# Createathon_2018.net
KiCad netlist of a schematic drawn in EAGLE
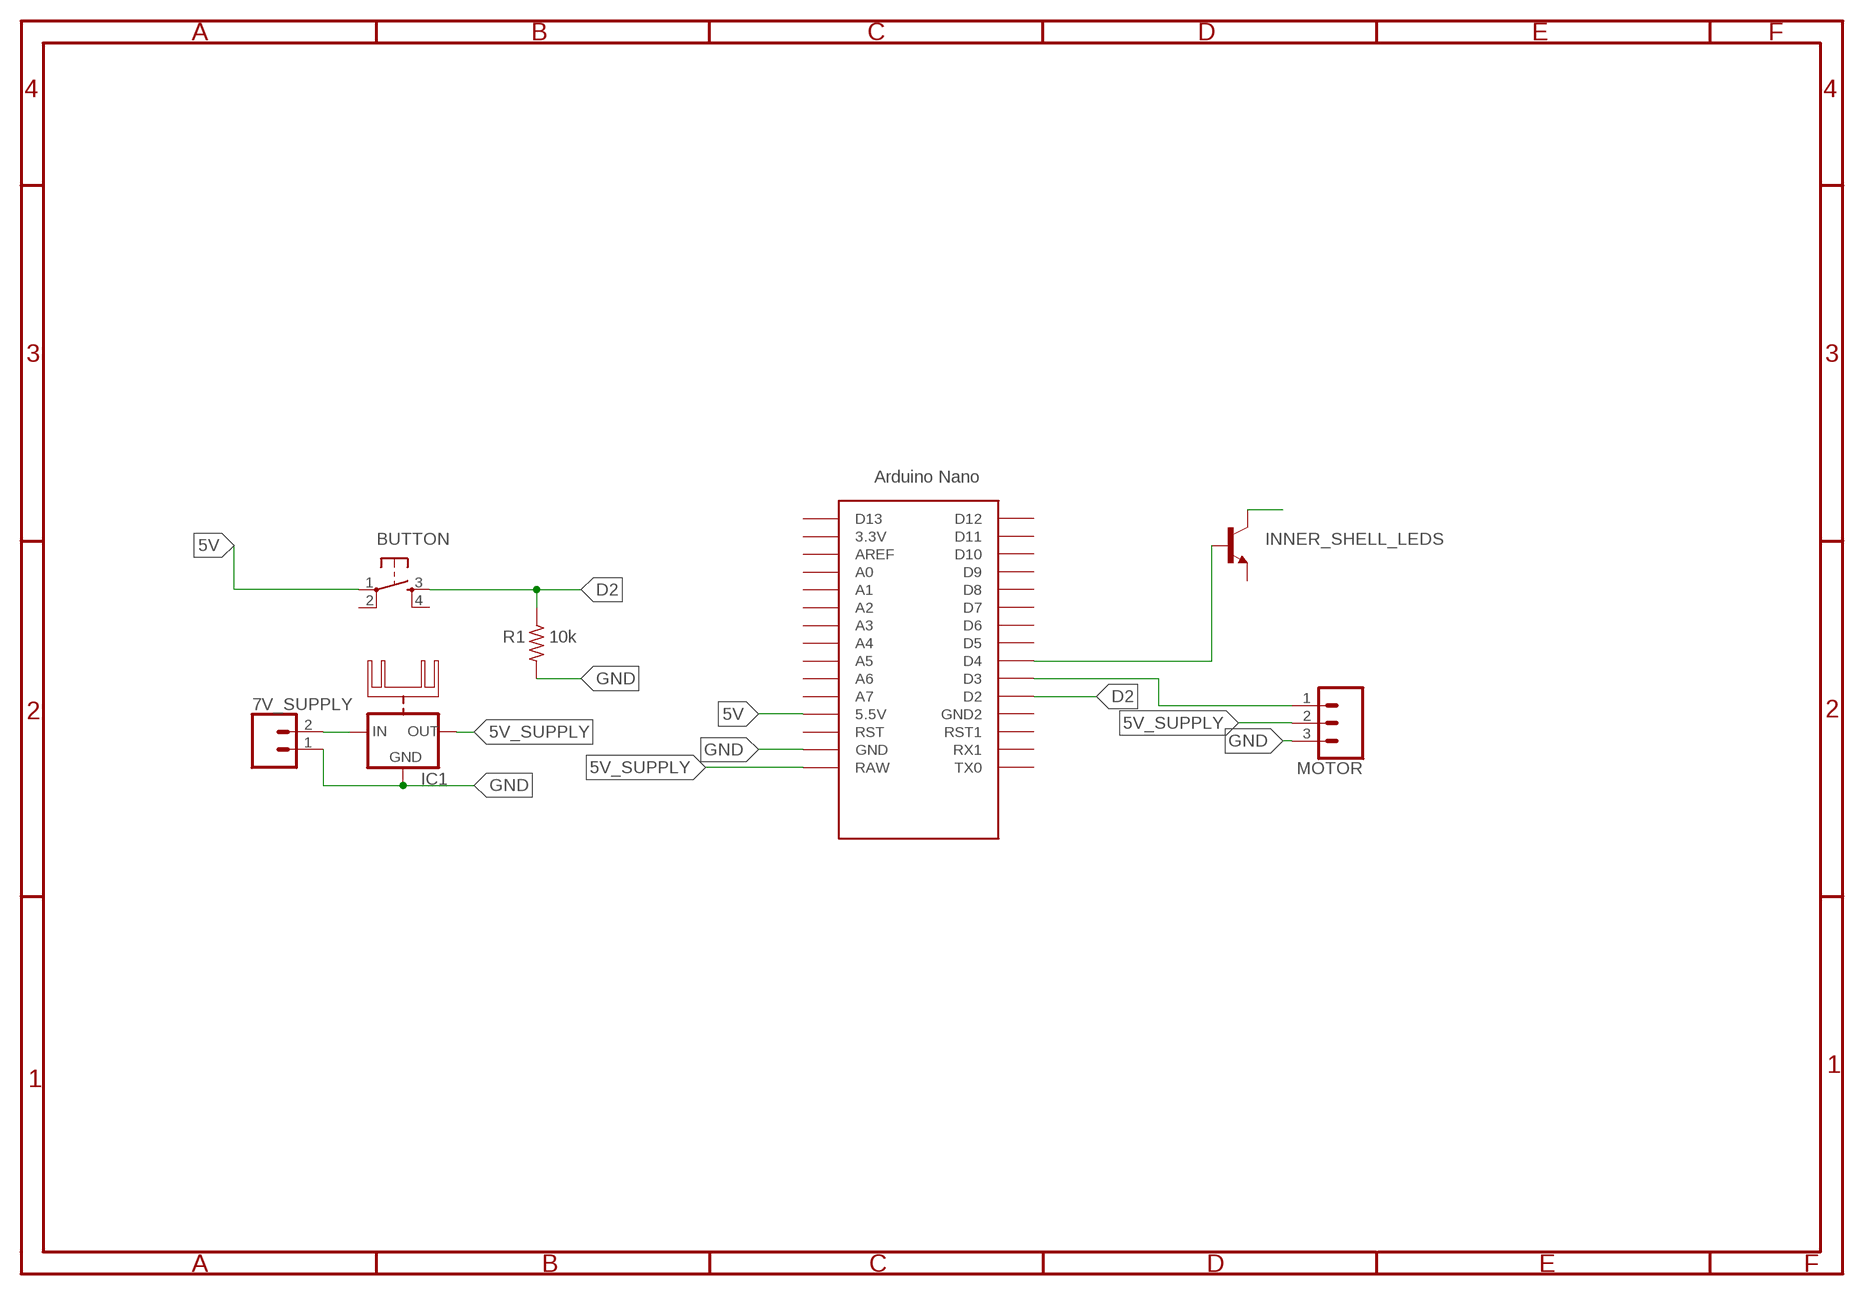
[diagram p0: schematic, sheet 1]

(export (version "E")
  (design (tool "Eeschema 10.0.6"))
  (components
    (comp (ref "7V_SUPPLY")
      (value "CONN_02")
      (footprint "eagle-import:1X02")
      (libsource (lib "eagle-import") (part "CONN_02"))
    )
    (comp (ref "BUTTON")
      (value "TAC_SWITCHPTH")
      (footprint "eagle-import:TACTILE-PTH")
      (libsource (lib "eagle-import") (part "TAC_SWITCHPTH"))
    )
    (comp (ref "IC1")
      (value "78XXH")
      (footprint "eagle-import:78XXH")
      (libsource (lib "eagle-import") (part "78XXH"))
    )
    (comp (ref "INNER_SHELL_LEDS")
      (value "TRANSISTOR_NPNTO92")
      (footprint "eagle-import:TO-92")
      (libsource (lib "eagle-import") (part "TRANSISTOR_NPNTO92"))
    )
    (comp (ref "MOTOR")
      (value "CONN_03")
      (footprint "eagle-import:1X03")
      (libsource (lib "eagle-import") (part "CONN_03"))
    )
    (comp (ref "R1")
      (value "10k")
      (footprint "eagle-import:0204_7")
      (libsource (lib "eagle-import") (part "R-US_0204/7"))
    )
    (comp (ref "U$1")
      (value "NANO")
      (footprint "eagle-import:NANO")
      (libsource (lib "eagle-import") (part "NANO"))
    )
  )
  (nets
    (net (code "1") (name "5V") (class "Default")
      (node (ref "BUTTON") (pin "1") (pinfunction "1_1") (pintype "passive"))
      (node (ref "U$1") (pin "5V") (pinfunction "5.5V_5V") (pintype "bidirectional"))
    )
    (net (code "2") (name "5V_SUPPLY") (class "Default")
      (node (ref "IC1") (pin "OUT") (pinfunction "OUT_OUT") (pintype "passive"))
      (node (ref "MOTOR") (pin "2") (pinfunction "2_2") (pintype "passive"))
      (node (ref "U$1") (pin "RAW") (pinfunction "RAW_RAW") (pintype "bidirectional"))
    )
    (net (code "3") (name "D2") (class "Default")
      (node (ref "BUTTON") (pin "3") (pinfunction "3_3") (pintype "passive"))
      (node (ref "R1") (pin "1") (pinfunction "1_1") (pintype "passive"))
      (node (ref "U$1") (pin "D2") (pinfunction "D2_D2") (pintype "bidirectional"))
    )
    (net (code "4") (name "GND") (class "Default")
      (node (ref "7V_SUPPLY") (pin "1") (pinfunction "1_1") (pintype "passive"))
      (node (ref "IC1") (pin "GND") (pinfunction "GND_GND") (pintype "input"))
      (node (ref "MOTOR") (pin "3") (pinfunction "3_3") (pintype "passive"))
      (node (ref "R1") (pin "2") (pinfunction "2_2") (pintype "passive"))
      (node (ref "U$1") (pin "GND") (pinfunction "GND_GND") (pintype "bidirectional"))
    )
    (net (code "5") (name "Net-(7V_SUPPLY-Pad2)") (class "Default")
      (node (ref "7V_SUPPLY") (pin "2") (pinfunction "2_2") (pintype "passive"))
      (node (ref "IC1") (pin "IN") (pinfunction "IN_IN") (pintype "input"))
    )
    (net (code "6") (name "Net-(INNER_SHELL_LEDS-B)") (class "Default")
      (node (ref "INNER_SHELL_LEDS") (pin "2") (pinfunction "B_2") (pintype "passive"))
      (node (ref "U$1") (pin "D4") (pinfunction "D4_D4") (pintype "bidirectional"))
    )
    (net (code "7") (name "Net-(MOTOR-Pad1)") (class "Default")
      (node (ref "MOTOR") (pin "1") (pinfunction "1_1") (pintype "passive"))
      (node (ref "U$1") (pin "D3") (pinfunction "D3_D3") (pintype "bidirectional"))
    )
    (net (code "8") (name "unconnected-(BUTTON-Pad2)") (class "Default")
      (node (ref "BUTTON") (pin "2") (pinfunction "2_2") (pintype "passive"))
    )
    (net (code "9") (name "unconnected-(BUTTON-Pad4)") (class "Default")
      (node (ref "BUTTON") (pin "4") (pinfunction "4_4") (pintype "passive"))
    )
    (net (code "10") (name "unconnected-(INNER_SHELL_LEDS-C-Pad3)") (class "Default")
      (node (ref "INNER_SHELL_LEDS") (pin "3") (pinfunction "C_3") (pintype "passive"))
    )
    (net (code "11") (name "unconnected-(INNER_SHELL_LEDS-E-Pad1)") (class "Default")
      (node (ref "INNER_SHELL_LEDS") (pin "1") (pinfunction "E_1") (pintype "passive"))
    )
    (net (code "12") (name "unconnected-(U$1-GND2-PadGND1)") (class "Default")
      (node (ref "U$1") (pin "GND1") (pinfunction "GND2_GND1") (pintype "bidirectional"))
    )
    (net (code "13") (name "unconnected-(U$1-Pad3.3V)") (class "Default")
      (node (ref "U$1") (pin "3.3V") (pinfunction "3.3V_3.3V") (pintype "bidirectional"))
    )
    (net (code "14") (name "unconnected-(U$1-PadA0)") (class "Default")
      (node (ref "U$1") (pin "A0") (pinfunction "A0_A0") (pintype "bidirectional"))
    )
    (net (code "15") (name "unconnected-(U$1-PadA1)") (class "Default")
      (node (ref "U$1") (pin "A1") (pinfunction "A1_A1") (pintype "bidirectional"))
    )
    (net (code "16") (name "unconnected-(U$1-PadA2)") (class "Default")
      (node (ref "U$1") (pin "A2") (pinfunction "A2_A2") (pintype "bidirectional"))
    )
    (net (code "17") (name "unconnected-(U$1-PadA3)") (class "Default")
      (node (ref "U$1") (pin "A3") (pinfunction "A3_A3") (pintype "bidirectional"))
    )
    (net (code "18") (name "unconnected-(U$1-PadA4)") (class "Default")
      (node (ref "U$1") (pin "A4") (pinfunction "A4_A4") (pintype "bidirectional"))
    )
    (net (code "19") (name "unconnected-(U$1-PadA5)") (class "Default")
      (node (ref "U$1") (pin "A5") (pinfunction "A5_A5") (pintype "bidirectional"))
    )
    (net (code "20") (name "unconnected-(U$1-PadA6)") (class "Default")
      (node (ref "U$1") (pin "A6") (pinfunction "A6_A6") (pintype "bidirectional"))
    )
    (net (code "21") (name "unconnected-(U$1-PadA7)") (class "Default")
      (node (ref "U$1") (pin "A7") (pinfunction "A7_A7") (pintype "bidirectional"))
    )
    (net (code "22") (name "unconnected-(U$1-PadAREF)") (class "Default")
      (node (ref "U$1") (pin "AREF") (pinfunction "AREF_AREF") (pintype "bidirectional"))
    )
    (net (code "23") (name "unconnected-(U$1-PadD5)") (class "Default")
      (node (ref "U$1") (pin "D5") (pinfunction "D5_D5") (pintype "bidirectional"))
    )
    (net (code "24") (name "unconnected-(U$1-PadD6)") (class "Default")
      (node (ref "U$1") (pin "D6") (pinfunction "D6_D6") (pintype "bidirectional"))
    )
    (net (code "25") (name "unconnected-(U$1-PadD7)") (class "Default")
      (node (ref "U$1") (pin "D7") (pinfunction "D7_D7") (pintype "bidirectional"))
    )
    (net (code "26") (name "unconnected-(U$1-PadD8)") (class "Default")
      (node (ref "U$1") (pin "D8") (pinfunction "D8_D8") (pintype "bidirectional"))
    )
    (net (code "27") (name "unconnected-(U$1-PadD9)") (class "Default")
      (node (ref "U$1") (pin "D9") (pinfunction "D9_D9") (pintype "bidirectional"))
    )
    (net (code "28") (name "unconnected-(U$1-PadD10)") (class "Default")
      (node (ref "U$1") (pin "D10") (pinfunction "D10_D10") (pintype "bidirectional"))
    )
    (net (code "29") (name "unconnected-(U$1-PadD11)") (class "Default")
      (node (ref "U$1") (pin "D11") (pinfunction "D11_D11") (pintype "bidirectional"))
    )
    (net (code "30") (name "unconnected-(U$1-PadD12)") (class "Default")
      (node (ref "U$1") (pin "D12") (pinfunction "D12_D12") (pintype "bidirectional"))
    )
    (net (code "31") (name "unconnected-(U$1-PadD13)") (class "Default")
      (node (ref "U$1") (pin "D13") (pinfunction "D13_D13") (pintype "bidirectional"))
    )
    (net (code "32") (name "unconnected-(U$1-PadICSP1)") (class "Default")
      (node (ref "U$1") (pin "ICSP1") (pinfunction "ICSP1_ICSP1") (pintype "bidirectional"))
    )
    (net (code "33") (name "unconnected-(U$1-PadICSP2)") (class "Default")
      (node (ref "U$1") (pin "ICSP2") (pinfunction "ICSP2_ICSP2") (pintype "bidirectional"))
    )
    (net (code "34") (name "unconnected-(U$1-PadICSP3)") (class "Default")
      (node (ref "U$1") (pin "ICSP3") (pinfunction "ICSP3_ICSP3") (pintype "bidirectional"))
    )
    (net (code "35") (name "unconnected-(U$1-PadICSP4)") (class "Default")
      (node (ref "U$1") (pin "ICSP4") (pinfunction "ICSP4_ICSP4") (pintype "bidirectional"))
    )
    (net (code "36") (name "unconnected-(U$1-PadICSP5)") (class "Default")
      (node (ref "U$1") (pin "ICSP5") (pinfunction "ICSP5_ICSP5") (pintype "bidirectional"))
    )
    (net (code "37") (name "unconnected-(U$1-PadICSP6)") (class "Default")
      (node (ref "U$1") (pin "ICSP6") (pinfunction "ICSP6_ICSP6") (pintype "bidirectional"))
    )
    (net (code "38") (name "unconnected-(U$1-PadRST)") (class "Default")
      (node (ref "U$1") (pin "RST") (pinfunction "RST_RST") (pintype "bidirectional"))
    )
    (net (code "39") (name "unconnected-(U$1-PadRST1)") (class "Default")
      (node (ref "U$1") (pin "RST1") (pinfunction "RST1_RST1") (pintype "bidirectional"))
    )
    (net (code "40") (name "unconnected-(U$1-PadRX1)") (class "Default")
      (node (ref "U$1") (pin "RX1") (pinfunction "RX1_RX1") (pintype "bidirectional"))
    )
    (net (code "41") (name "unconnected-(U$1-PadTX0)") (class "Default")
      (node (ref "U$1") (pin "TX0") (pinfunction "TX0_TX0") (pintype "bidirectional"))
    )
  )
)
